# Reset_v1_0.net
KiCad netlist of a schematic drawn in EAGLE
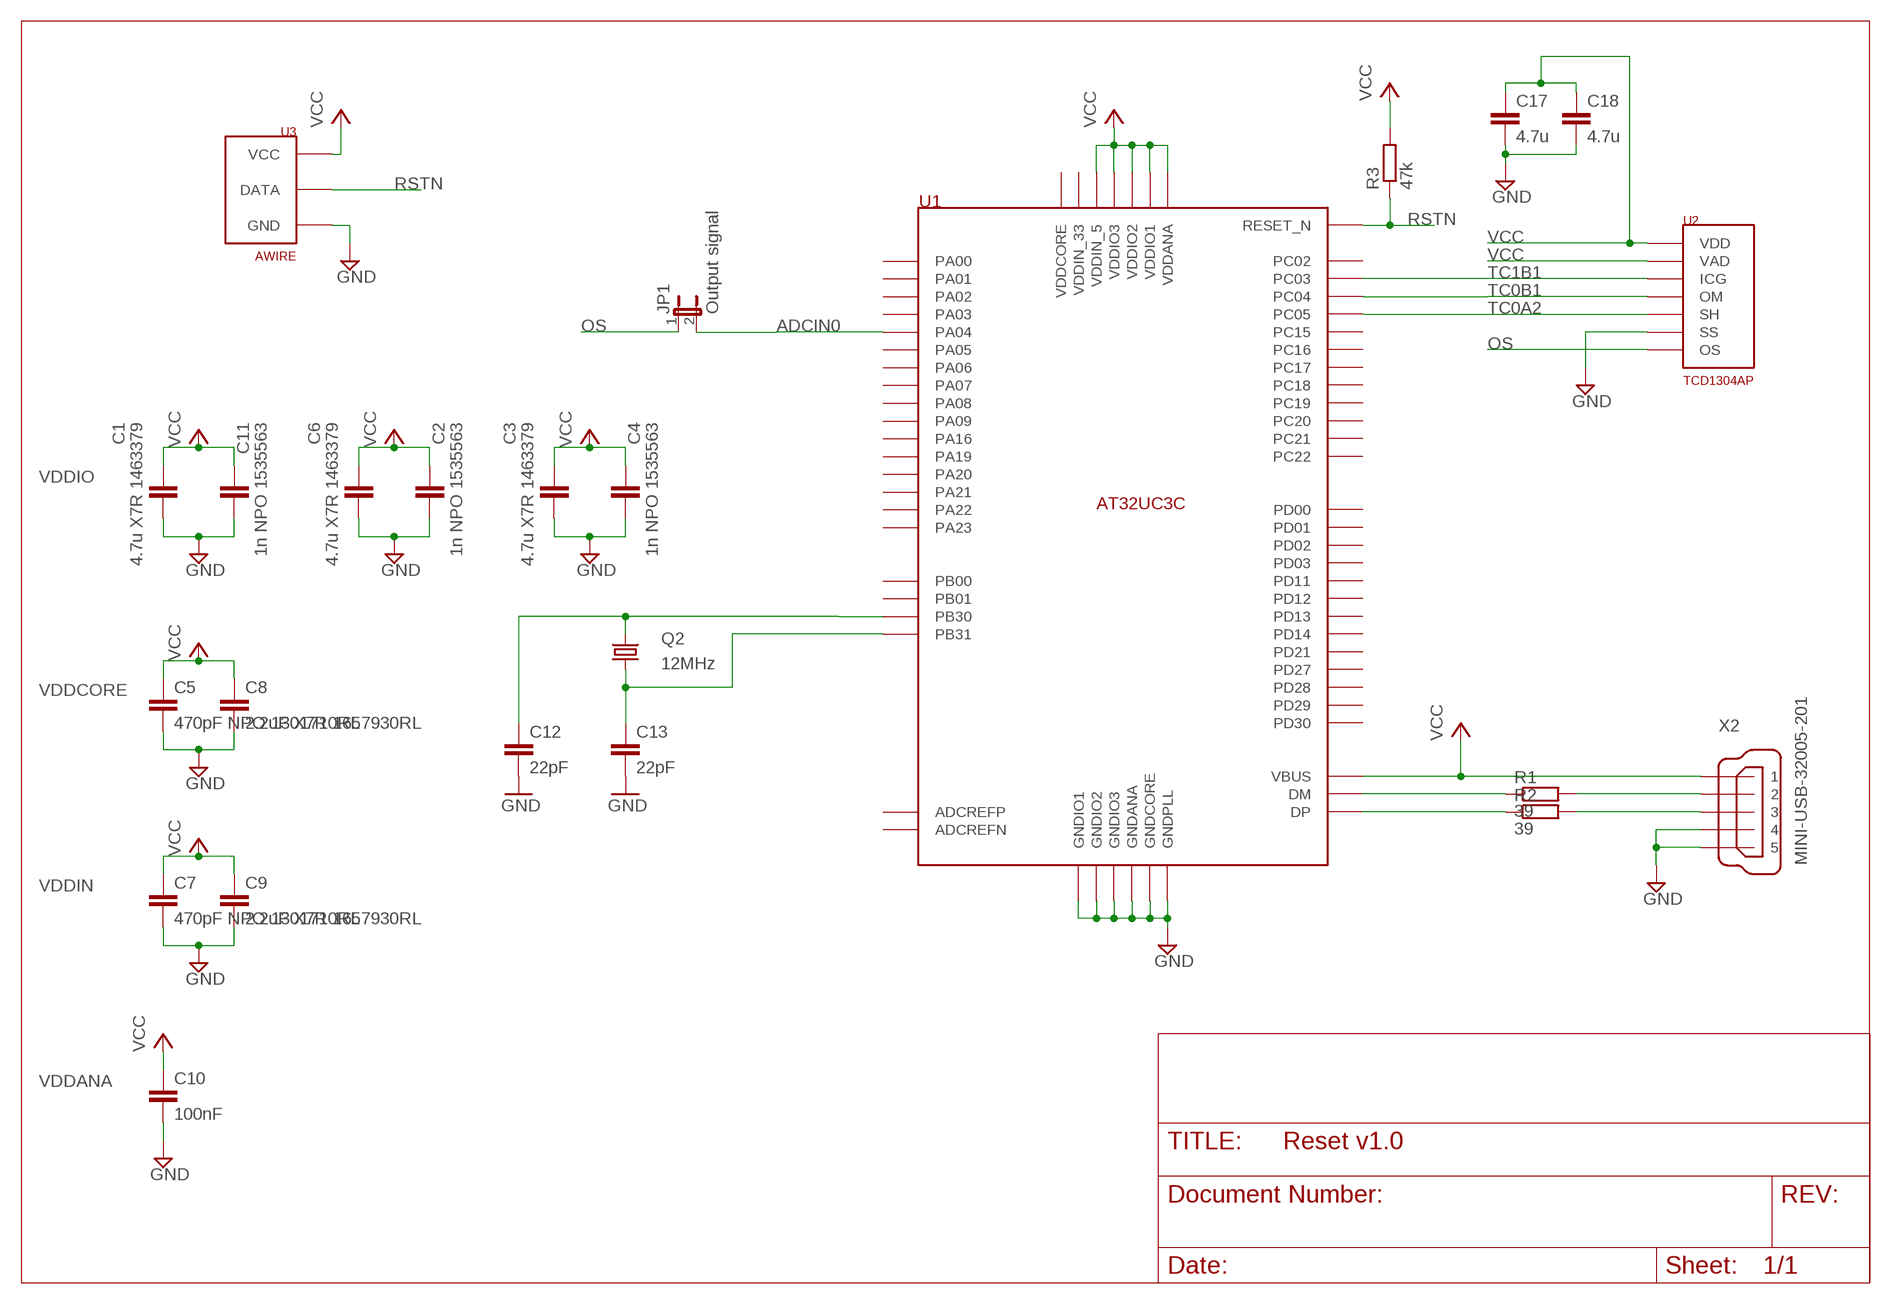
[diagram p0: schematic, sheet 1]

(export (version "E")
  (design (tool "Eeschema 10.0.6"))
  (components
    (comp (ref "C1")
      (value "4.7u X7R 1463379")
      (footprint "eagle-import:C0603")
      (libsource (lib "eagle-import") (part "C-EUC0603"))
    )
    (comp (ref "C2")
      (value "1n NPO 1535563")
      (footprint "eagle-import:C0402")
      (libsource (lib "eagle-import") (part "C-EUC0402"))
    )
    (comp (ref "C3")
      (value "4.7u X7R 1463379")
      (footprint "eagle-import:C0603")
      (libsource (lib "eagle-import") (part "C-EUC0603"))
    )
    (comp (ref "C4")
      (value "1n NPO 1535563")
      (footprint "eagle-import:C0402")
      (libsource (lib "eagle-import") (part "C-EUC0402"))
    )
    (comp (ref "C5")
      (value "470pF NPO 1301710RL")
      (footprint "eagle-import:C0603")
      (libsource (lib "eagle-import") (part "C-EUC0603"))
    )
    (comp (ref "C6")
      (value "4.7u X7R 1463379")
      (footprint "eagle-import:C0603")
      (libsource (lib "eagle-import") (part "C-EUC0603"))
    )
    (comp (ref "C7")
      (value "470pF NPO 1301710RL")
      (footprint "eagle-import:C0603")
      (libsource (lib "eagle-import") (part "C-EUC0603"))
    )
    (comp (ref "C8")
      (value "2.2uF X7R 1657930RL")
      (footprint "eagle-import:C0603")
      (libsource (lib "eagle-import") (part "C-EUC0603"))
    )
    (comp (ref "C9")
      (value "2.2uF X7R 1657930RL")
      (footprint "eagle-import:C0603")
      (libsource (lib "eagle-import") (part "C-EUC0603"))
    )
    (comp (ref "C10")
      (value "100nF")
      (footprint "eagle-import:C0603")
      (libsource (lib "eagle-import") (part "C-EUC0603"))
    )
    (comp (ref "C11")
      (value "1n NPO 1535563")
      (footprint "eagle-import:C0402")
      (libsource (lib "eagle-import") (part "C-EUC0402"))
    )
    (comp (ref "C12")
      (value "22pF")
      (footprint "eagle-import:C0402")
      (libsource (lib "eagle-import") (part "C-EUC0402"))
    )
    (comp (ref "C13")
      (value "22pF")
      (footprint "eagle-import:C0402")
      (libsource (lib "eagle-import") (part "C-EUC0402"))
    )
    (comp (ref "C17")
      (value "4.7u")
      (footprint "eagle-import:C0805")
      (libsource (lib "eagle-import") (part "resistor_C-EUC0805"))
    )
    (comp (ref "C18")
      (value "4.7u")
      (footprint "eagle-import:C0805")
      (libsource (lib "eagle-import") (part "resistor_C-EUC0805"))
    )
    (comp (ref "JP1")
      (value "Output signal")
      (footprint "eagle-import:JP1")
      (libsource (lib "eagle-import") (part "JP1E"))
    )
    (comp (ref "Q2")
      (value "12MHz")
      (footprint "eagle-import:CRYSTAL-SMD-5X3")
      (libsource (lib "eagle-import") (part "CRYSTAL5X3"))
    )
    (comp (ref "R1")
      (value "39")
      (footprint "eagle-import:R0603")
      (libsource (lib "eagle-import") (part "R-EU_R0603"))
    )
    (comp (ref "R2")
      (value "39")
      (footprint "eagle-import:R0603")
      (libsource (lib "eagle-import") (part "R-EU_R0603"))
    )
    (comp (ref "R3")
      (value "47k")
      (footprint "eagle-import:R0603")
      (libsource (lib "eagle-import") (part "R-EU_R0603"))
    )
    (comp (ref "U1")
      (value "AT32UC3C")
      (footprint "eagle-import:TQFP64")
      (libsource (lib "eagle-import") (part "AT32UC3C"))
    )
    (comp (ref "U2")
      (value "TCD1304AP")
      (footprint "eagle-import:TCD1304AP")
      (libsource (lib "eagle-import") (part "TCD1304AP"))
    )
    (comp (ref "U3")
      (value "AWIRE")
      (footprint "eagle-import:AWIRE")
      (libsource (lib "eagle-import") (part "AWIRE"))
    )
    (comp (ref "X2")
      (value "MINI-USB-32005-201")
      (footprint "eagle-import:32005-201")
      (libsource (lib "eagle-import") (part "MINI-USB-32005-201"))
    )
  )
  (nets
    (net (code "1") (name "/ADCIN0") (class "Default")
      (node (ref "JP1") (pin "2") (pinfunction "2_2") (pintype "passive"))
      (node (ref "U1") (pin "P$7") (pinfunction "PA04_P$7") (pintype "bidirectional"))
    )
    (net (code "2") (name "/OS") (class "Default")
      (node (ref "JP1") (pin "1") (pinfunction "1_1") (pintype "passive"))
      (node (ref "U2") (pin "P$21") (pinfunction "OS_P$21") (pintype "bidirectional"))
    )
    (net (code "3") (name "/RSTN") (class "Default")
      (node (ref "R3") (pin "1") (pinfunction "1_1") (pintype "passive"))
      (node (ref "U1") (pin "P$64") (pinfunction "RESET_N_P$64") (pintype "bidirectional"))
      (node (ref "U3") (pin "P$2") (pinfunction "DATA_P$2") (pintype "bidirectional"))
    )
    (net (code "4") (name "/TC0A2") (class "Default")
      (node (ref "U1") (pin "P$38") (pinfunction "PC05_P$38") (pintype "bidirectional"))
      (node (ref "U2") (pin "P$5") (pinfunction "SH_P$5") (pintype "bidirectional"))
    )
    (net (code "5") (name "/TC0B1") (class "Default")
      (node (ref "U1") (pin "P$37") (pinfunction "PC04_P$37") (pintype "bidirectional"))
      (node (ref "U2") (pin "P$4") (pinfunction "OM_P$4") (pintype "bidirectional"))
    )
    (net (code "6") (name "/TC1B1") (class "Default")
      (node (ref "U1") (pin "P$34") (pinfunction "PC03_P$34") (pintype "bidirectional"))
      (node (ref "U2") (pin "P$3") (pinfunction "ICG_P$3") (pintype "bidirectional"))
    )
    (net (code "7") (name "GND") (class "Default")
      (node (ref "C1") (pin "2") (pinfunction "2_2") (pintype "passive"))
      (node (ref "C10") (pin "2") (pinfunction "2_2") (pintype "passive"))
      (node (ref "C11") (pin "2") (pinfunction "2_2") (pintype "passive"))
      (node (ref "C12") (pin "2") (pinfunction "2_2") (pintype "passive"))
      (node (ref "C13") (pin "2") (pinfunction "2_2") (pintype "passive"))
      (node (ref "C17") (pin "2") (pinfunction "2_2") (pintype "passive"))
      (node (ref "C18") (pin "2") (pinfunction "2_2") (pintype "passive"))
      (node (ref "C2") (pin "2") (pinfunction "2_2") (pintype "passive"))
      (node (ref "C3") (pin "2") (pinfunction "2_2") (pintype "passive"))
      (node (ref "C4") (pin "2") (pinfunction "2_2") (pintype "passive"))
      (node (ref "C5") (pin "2") (pinfunction "2_2") (pintype "passive"))
      (node (ref "C6") (pin "2") (pinfunction "2_2") (pintype "passive"))
      (node (ref "C7") (pin "2") (pinfunction "2_2") (pintype "passive"))
      (node (ref "C8") (pin "2") (pinfunction "2_2") (pintype "passive"))
      (node (ref "C9") (pin "2") (pinfunction "2_2") (pintype "passive"))
      (node (ref "U1") (pin "P$17") (pinfunction "GNDANA_P$17") (pintype "bidirectional"))
      (node (ref "U1") (pin "P$26") (pinfunction "GNDPLL_P$26") (pintype "bidirectional"))
      (node (ref "U1") (pin "P$30") (pinfunction "GNDCORE_P$30") (pintype "bidirectional"))
      (node (ref "U1") (pin "P$36") (pinfunction "GNDIO2_P$36") (pintype "bidirectional"))
      (node (ref "U1") (pin "P$52") (pinfunction "GNDIO3_P$52") (pintype "bidirectional"))
      (node (ref "U1") (pin "P$6") (pinfunction "GNDIO1_P$6") (pintype "bidirectional"))
      (node (ref "U2") (pin "P$22") (pinfunction "SS_P$22") (pintype "bidirectional"))
      (node (ref "U3") (pin "P$3") (pinfunction "GND_P$3") (pintype "bidirectional"))
      (node (ref "X2") (pin "4") (pinfunction "4_4") (pintype "passive"))
      (node (ref "X2") (pin "5") (pinfunction "5_5") (pintype "passive"))
    )
    (net (code "8") (name "Net-(Q2-2)") (class "Default")
      (node (ref "C12") (pin "1") (pinfunction "1_1") (pintype "passive"))
      (node (ref "Q2") (pin "3") (pinfunction "2_3") (pintype "passive"))
      (node (ref "U1") (pin "P$31") (pinfunction "PB30_P$31") (pintype "bidirectional"))
    )
    (net (code "9") (name "Net-(R1-Pad2)") (class "Default")
      (node (ref "R1") (pin "2") (pinfunction "2_2") (pintype "passive"))
      (node (ref "X2") (pin "2") (pinfunction "2_2") (pintype "passive"))
    )
    (net (code "10") (name "Net-(R2-Pad2)") (class "Default")
      (node (ref "R2") (pin "2") (pinfunction "2_2") (pintype "passive"))
      (node (ref "X2") (pin "3") (pinfunction "3_3") (pintype "passive"))
    )
    (net (code "11") (name "Net-(U1-DM)") (class "Default")
      (node (ref "R1") (pin "1") (pinfunction "1_1") (pintype "passive"))
      (node (ref "U1") (pin "P$24") (pinfunction "DM_P$24") (pintype "bidirectional"))
    )
    (net (code "12") (name "Net-(U1-DP)") (class "Default")
      (node (ref "R2") (pin "1") (pinfunction "1_1") (pintype "passive"))
      (node (ref "U1") (pin "P$25") (pinfunction "DP_P$25") (pintype "bidirectional"))
    )
    (net (code "13") (name "Net-(U1-PB31)") (class "Default")
      (node (ref "C13") (pin "1") (pinfunction "1_1") (pintype "passive"))
      (node (ref "Q2") (pin "1") (pinfunction "1_1") (pintype "passive"))
      (node (ref "U1") (pin "P$32") (pinfunction "PB31_P$32") (pintype "bidirectional"))
    )
    (net (code "14") (name "VCC") (class "Default")
      (node (ref "C1") (pin "1") (pinfunction "1_1") (pintype "passive"))
      (node (ref "C10") (pin "1") (pinfunction "1_1") (pintype "passive"))
      (node (ref "C11") (pin "1") (pinfunction "1_1") (pintype "passive"))
      (node (ref "C17") (pin "1") (pinfunction "1_1") (pintype "passive"))
      (node (ref "C18") (pin "1") (pinfunction "1_1") (pintype "passive"))
      (node (ref "C2") (pin "1") (pinfunction "1_1") (pintype "passive"))
      (node (ref "C3") (pin "1") (pinfunction "1_1") (pintype "passive"))
      (node (ref "C4") (pin "1") (pinfunction "1_1") (pintype "passive"))
      (node (ref "C5") (pin "1") (pinfunction "1_1") (pintype "passive"))
      (node (ref "C6") (pin "1") (pinfunction "1_1") (pintype "passive"))
      (node (ref "C7") (pin "1") (pinfunction "1_1") (pintype "passive"))
      (node (ref "C8") (pin "1") (pinfunction "1_1") (pintype "passive"))
      (node (ref "C9") (pin "1") (pinfunction "1_1") (pintype "passive"))
      (node (ref "R3") (pin "2") (pinfunction "2_2") (pintype "passive"))
      (node (ref "U1") (pin "P$18") (pinfunction "VDDANA_P$18") (pintype "bidirectional"))
      (node (ref "U1") (pin "P$23") (pinfunction "VBUS_P$23") (pintype "bidirectional"))
      (node (ref "U1") (pin "P$27") (pinfunction "VDDIN_5_P$27") (pintype "bidirectional"))
      (node (ref "U1") (pin "P$35") (pinfunction "VDDIO2_P$35") (pintype "bidirectional"))
      (node (ref "U1") (pin "P$5") (pinfunction "VDDIO1_P$5") (pintype "bidirectional"))
      (node (ref "U1") (pin "P$51") (pinfunction "VDDIO3_P$51") (pintype "bidirectional"))
      (node (ref "U2") (pin "P$1") (pinfunction "VDD_P$1") (pintype "bidirectional"))
      (node (ref "U2") (pin "P$2") (pinfunction "VAD_P$2") (pintype "bidirectional"))
      (node (ref "U3") (pin "P$1") (pinfunction "VCC_P$1") (pintype "bidirectional"))
      (node (ref "X2") (pin "1") (pinfunction "1_1") (pintype "passive"))
    )
    (net (code "15") (name "unconnected-(U1-ADCREFN-PadP$15)") (class "Default")
      (node (ref "U1") (pin "P$15") (pinfunction "ADCREFN_P$15") (pintype "bidirectional"))
    )
    (net (code "16") (name "unconnected-(U1-ADCREFP-PadP$14)") (class "Default")
      (node (ref "U1") (pin "P$14") (pinfunction "ADCREFP_P$14") (pintype "bidirectional"))
    )
    (net (code "17") (name "unconnected-(U1-PA00-PadP$1)") (class "Default")
      (node (ref "U1") (pin "P$1") (pinfunction "PA00_P$1") (pintype "bidirectional"))
    )
    (net (code "18") (name "unconnected-(U1-PA01-PadP$2)") (class "Default")
      (node (ref "U1") (pin "P$2") (pinfunction "PA01_P$2") (pintype "bidirectional"))
    )
    (net (code "19") (name "unconnected-(U1-PA02-PadP$3)") (class "Default")
      (node (ref "U1") (pin "P$3") (pinfunction "PA02_P$3") (pintype "bidirectional"))
    )
    (net (code "20") (name "unconnected-(U1-PA03-PadP$4)") (class "Default")
      (node (ref "U1") (pin "P$4") (pinfunction "PA03_P$4") (pintype "bidirectional"))
    )
    (net (code "21") (name "unconnected-(U1-PA05-PadP$8)") (class "Default")
      (node (ref "U1") (pin "P$8") (pinfunction "PA05_P$8") (pintype "bidirectional"))
    )
    (net (code "22") (name "unconnected-(U1-PA06-PadP$9)") (class "Default")
      (node (ref "U1") (pin "P$9") (pinfunction "PA06_P$9") (pintype "bidirectional"))
    )
    (net (code "23") (name "unconnected-(U1-PA07-PadP$10)") (class "Default")
      (node (ref "U1") (pin "P$10") (pinfunction "PA07_P$10") (pintype "bidirectional"))
    )
    (net (code "24") (name "unconnected-(U1-PA08-PadP$11)") (class "Default")
      (node (ref "U1") (pin "P$11") (pinfunction "PA08_P$11") (pintype "bidirectional"))
    )
    (net (code "25") (name "unconnected-(U1-PA09-PadP$12)") (class "Default")
      (node (ref "U1") (pin "P$12") (pinfunction "PA09_P$12") (pintype "bidirectional"))
    )
    (net (code "26") (name "unconnected-(U1-PA16-PadP$13)") (class "Default")
      (node (ref "U1") (pin "P$13") (pinfunction "PA16_P$13") (pintype "bidirectional"))
    )
    (net (code "27") (name "unconnected-(U1-PA19-PadP$16)") (class "Default")
      (node (ref "U1") (pin "P$16") (pinfunction "PA19_P$16") (pintype "bidirectional"))
    )
    (net (code "28") (name "unconnected-(U1-PA20-PadP$19)") (class "Default")
      (node (ref "U1") (pin "P$19") (pinfunction "PA20_P$19") (pintype "bidirectional"))
    )
    (net (code "29") (name "unconnected-(U1-PA21-PadP$20)") (class "Default")
      (node (ref "U1") (pin "P$20") (pinfunction "PA21_P$20") (pintype "bidirectional"))
    )
    (net (code "30") (name "unconnected-(U1-PA22-PadP$21)") (class "Default")
      (node (ref "U1") (pin "P$21") (pinfunction "PA22_P$21") (pintype "bidirectional"))
    )
    (net (code "31") (name "unconnected-(U1-PA23-PadP$22)") (class "Default")
      (node (ref "U1") (pin "P$22") (pinfunction "PA23_P$22") (pintype "bidirectional"))
    )
    (net (code "32") (name "unconnected-(U1-PB00-PadP$62)") (class "Default")
      (node (ref "U1") (pin "P$62") (pinfunction "PB00_P$62") (pintype "bidirectional"))
    )
    (net (code "33") (name "unconnected-(U1-PB01-PadP$63)") (class "Default")
      (node (ref "U1") (pin "P$63") (pinfunction "PB01_P$63") (pintype "bidirectional"))
    )
    (net (code "34") (name "unconnected-(U1-PC02-PadP$33)") (class "Default")
      (node (ref "U1") (pin "P$33") (pinfunction "PC02_P$33") (pintype "bidirectional"))
    )
    (net (code "35") (name "unconnected-(U1-PC15-PadP$39)") (class "Default")
      (node (ref "U1") (pin "P$39") (pinfunction "PC15_P$39") (pintype "bidirectional"))
    )
    (net (code "36") (name "unconnected-(U1-PC16-PadP$40)") (class "Default")
      (node (ref "U1") (pin "P$40") (pinfunction "PC16_P$40") (pintype "bidirectional"))
    )
    (net (code "37") (name "unconnected-(U1-PC17-PadP$41)") (class "Default")
      (node (ref "U1") (pin "P$41") (pinfunction "PC17_P$41") (pintype "bidirectional"))
    )
    (net (code "38") (name "unconnected-(U1-PC18-PadP$42)") (class "Default")
      (node (ref "U1") (pin "P$42") (pinfunction "PC18_P$42") (pintype "bidirectional"))
    )
    (net (code "39") (name "unconnected-(U1-PC19-PadP$43)") (class "Default")
      (node (ref "U1") (pin "P$43") (pinfunction "PC19_P$43") (pintype "bidirectional"))
    )
    (net (code "40") (name "unconnected-(U1-PC20-PadP$44)") (class "Default")
      (node (ref "U1") (pin "P$44") (pinfunction "PC20_P$44") (pintype "bidirectional"))
    )
    (net (code "41") (name "unconnected-(U1-PC21-PadP$45)") (class "Default")
      (node (ref "U1") (pin "P$45") (pinfunction "PC21_P$45") (pintype "bidirectional"))
    )
    (net (code "42") (name "unconnected-(U1-PC22-PadP$46)") (class "Default")
      (node (ref "U1") (pin "P$46") (pinfunction "PC22_P$46") (pintype "bidirectional"))
    )
    (net (code "43") (name "unconnected-(U1-PD00-PadP$47)") (class "Default")
      (node (ref "U1") (pin "P$47") (pinfunction "PD00_P$47") (pintype "bidirectional"))
    )
    (net (code "44") (name "unconnected-(U1-PD01-PadP$48)") (class "Default")
      (node (ref "U1") (pin "P$48") (pinfunction "PD01_P$48") (pintype "bidirectional"))
    )
    (net (code "45") (name "unconnected-(U1-PD02-PadP$49)") (class "Default")
      (node (ref "U1") (pin "P$49") (pinfunction "PD02_P$49") (pintype "bidirectional"))
    )
    (net (code "46") (name "unconnected-(U1-PD03-PadP$50)") (class "Default")
      (node (ref "U1") (pin "P$50") (pinfunction "PD03_P$50") (pintype "bidirectional"))
    )
    (net (code "47") (name "unconnected-(U1-PD11-PadP$53)") (class "Default")
      (node (ref "U1") (pin "P$53") (pinfunction "PD11_P$53") (pintype "bidirectional"))
    )
    (net (code "48") (name "unconnected-(U1-PD12-PadP$54)") (class "Default")
      (node (ref "U1") (pin "P$54") (pinfunction "PD12_P$54") (pintype "bidirectional"))
    )
    (net (code "49") (name "unconnected-(U1-PD13-PadP$55)") (class "Default")
      (node (ref "U1") (pin "P$55") (pinfunction "PD13_P$55") (pintype "bidirectional"))
    )
    (net (code "50") (name "unconnected-(U1-PD14-PadP$56)") (class "Default")
      (node (ref "U1") (pin "P$56") (pinfunction "PD14_P$56") (pintype "bidirectional"))
    )
    (net (code "51") (name "unconnected-(U1-PD21-PadP$57)") (class "Default")
      (node (ref "U1") (pin "P$57") (pinfunction "PD21_P$57") (pintype "bidirectional"))
    )
    (net (code "52") (name "unconnected-(U1-PD27-PadP$58)") (class "Default")
      (node (ref "U1") (pin "P$58") (pinfunction "PD27_P$58") (pintype "bidirectional"))
    )
    (net (code "53") (name "unconnected-(U1-PD28-PadP$59)") (class "Default")
      (node (ref "U1") (pin "P$59") (pinfunction "PD28_P$59") (pintype "bidirectional"))
    )
    (net (code "54") (name "unconnected-(U1-PD29-PadP$60)") (class "Default")
      (node (ref "U1") (pin "P$60") (pinfunction "PD29_P$60") (pintype "bidirectional"))
    )
    (net (code "55") (name "unconnected-(U1-PD30-PadP$61)") (class "Default")
      (node (ref "U1") (pin "P$61") (pinfunction "PD30_P$61") (pintype "bidirectional"))
    )
    (net (code "56") (name "unconnected-(U1-VDDCORE-PadP$29)") (class "Default")
      (node (ref "U1") (pin "P$29") (pinfunction "VDDCORE_P$29") (pintype "bidirectional"))
    )
    (net (code "57") (name "unconnected-(U1-VDDIN_33-PadP$28)") (class "Default")
      (node (ref "U1") (pin "P$28") (pinfunction "VDDIN_33_P$28") (pintype "bidirectional"))
    )
  )
)
